# Pr_actica_1.net
KiCad netlist of a schematic drawn in EAGLE
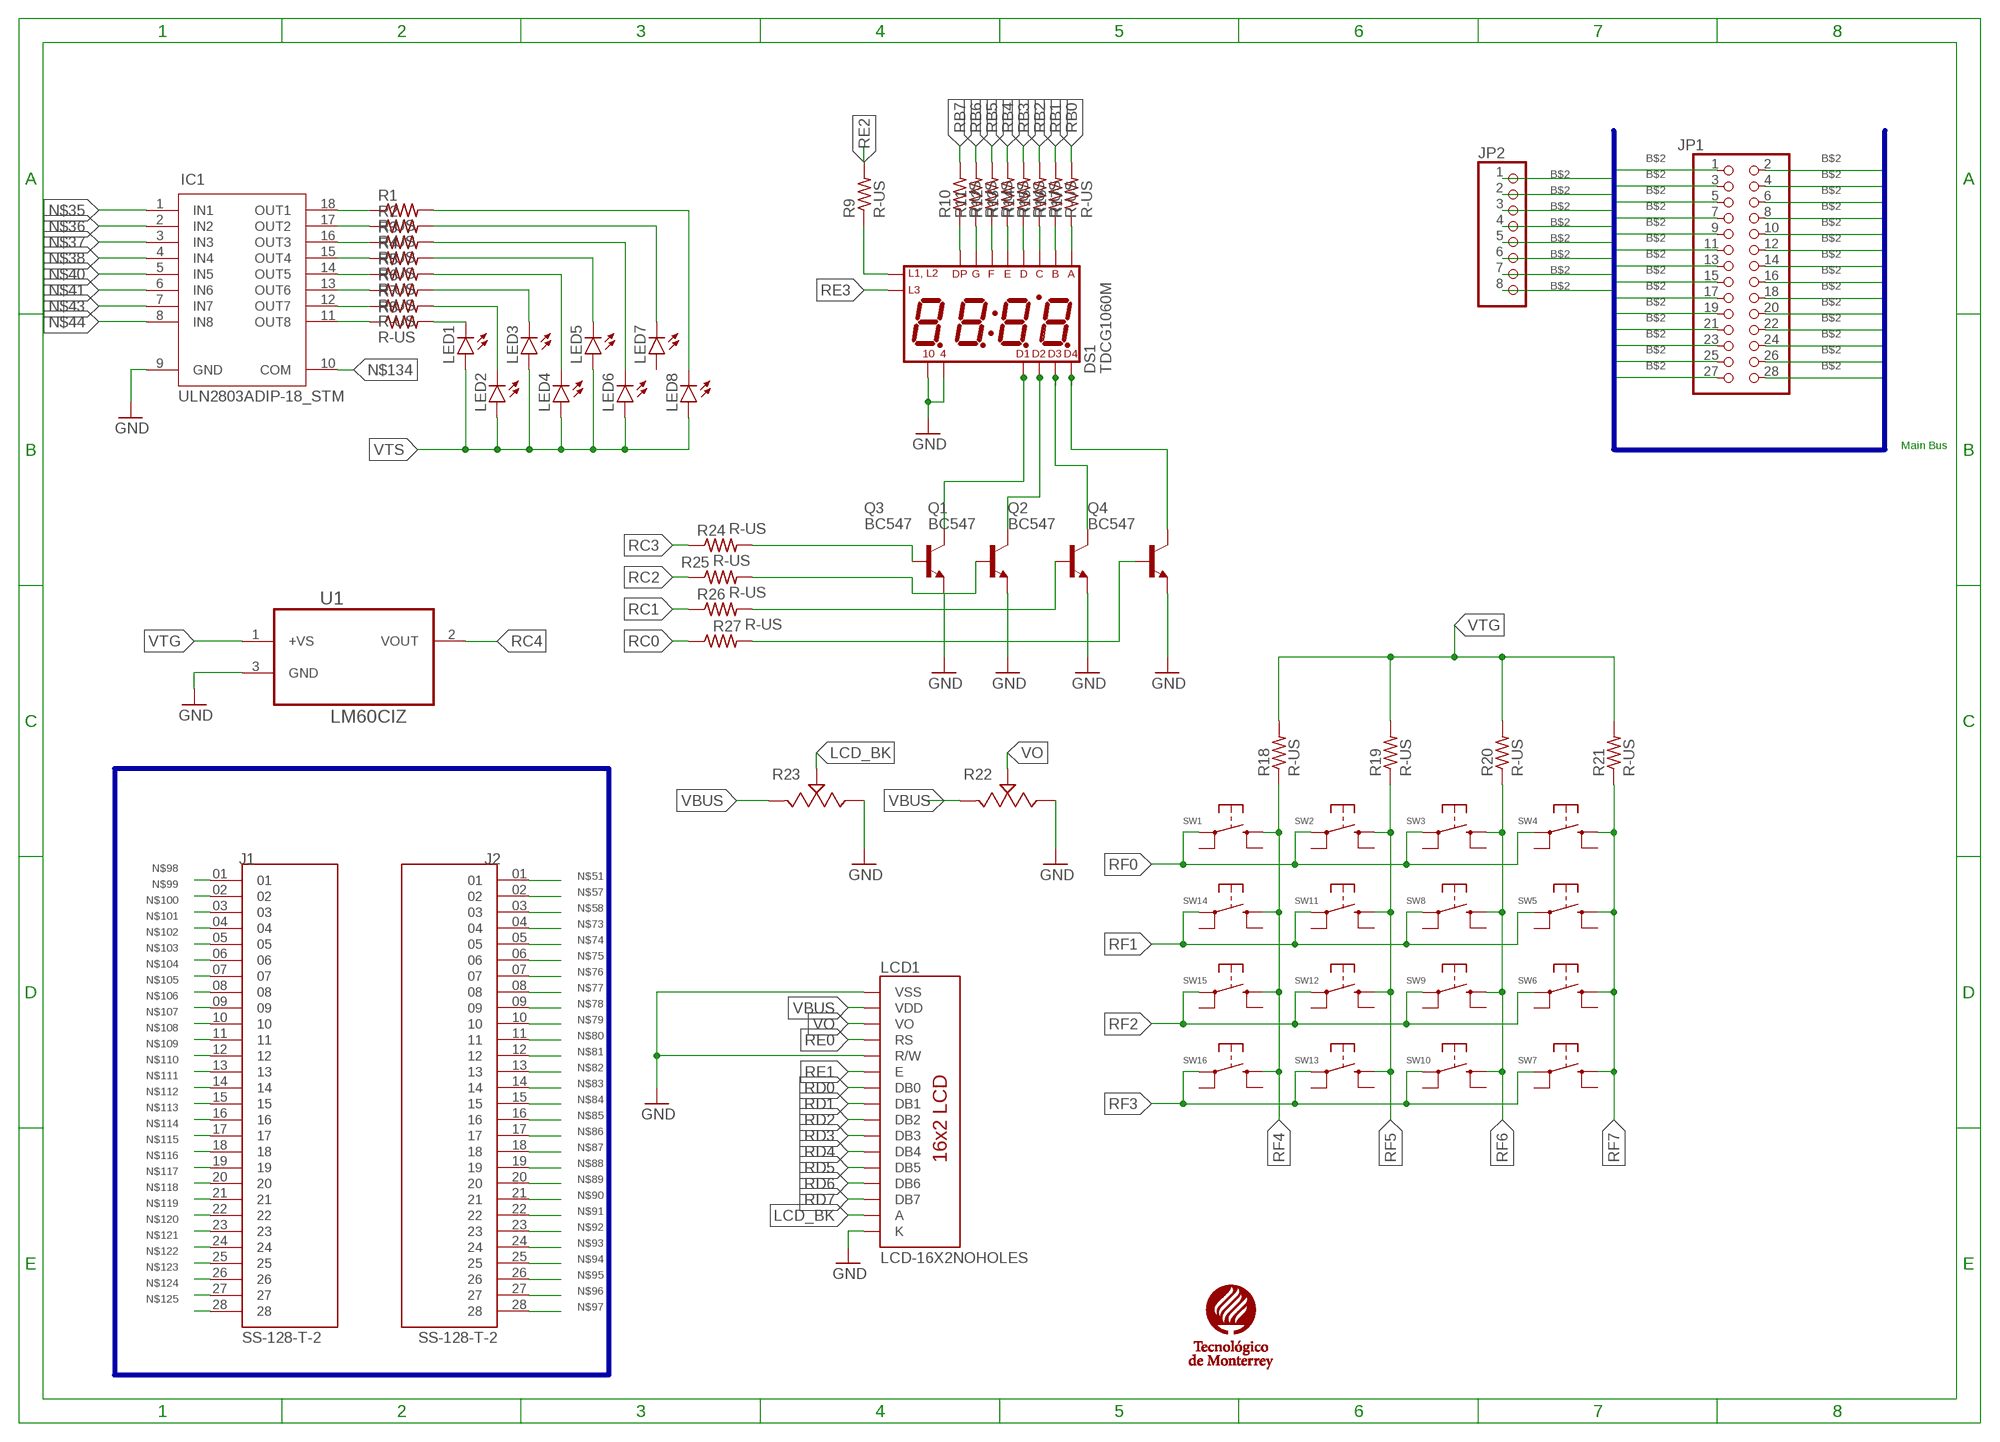
[diagram p0: schematic, sheet 1]

(export (version "E")
  (design (tool "Eeschema 10.0.6"))
  (components
    (comp (ref "DS1")
      (value "TDCG1060M")
      (footprint "eagle-import:DISPLAY_TDCG1060M")
      (fields (field (name "DIGI-KEY_PART_NUMBER") "TDCG1060M-ND") (field (name "MF") "Vishay"))
      (libsource (lib "eagle-import") (part "TDCG1060M"))
    )
    (comp (ref "IC1")
      (value "ULN2803ADIP-18_STM")
      (footprint "eagle-import:DIP-18_STM")
      (fields
        (field (name "MANUFACTURER_PART_NUMBER") "ULN2803A")
        (field (name "COPYRIGHT") "Copyright (C) 2022 Ultra Librarian. All rights reserved.")
      )
      (libsource (lib "eagle-import") (part "ULN2803ADIP-18_STM"))
    )
    (comp (ref "J1")
      (value "SS-128-T-2")
      (footprint "eagle-import:SAMTEC_SS-128-T-2")
      (fields (field (name "DIGI-KEY_PART_NUMBER") "SAM1117-28-ND") (field (name "MF") "Samtec"))
      (libsource (lib "eagle-import") (part "SS-128-T-2"))
    )
    (comp (ref "J2")
      (value "SS-128-T-2")
      (footprint "eagle-import:SAMTEC_SS-128-T-2")
      (fields (field (name "DIGI-KEY_PART_NUMBER") "SAM1117-28-ND") (field (name "MF") "Samtec"))
      (libsource (lib "eagle-import") (part "SS-128-T-2"))
    )
    (comp (ref "JP1")
      (value "PINHD-2X14-CB")
      (footprint "eagle-import:2X14-BIG")
      (libsource (lib "eagle-import") (part "PINHD-2X14-CB"))
    )
    (comp (ref "JP2")
      (value "PINHD-1X8BIG")
      (footprint "eagle-import:1X08-BIG")
      (libsource (lib "eagle-import") (part "PINHD-1X8BIG"))
    )
    (comp (ref "LCD1")
      (value "LCD-16X2NOHOLES")
      (footprint "eagle-import:LCD-16X2_NOHOLESNOSILK")
      (libsource (lib "eagle-import") (part "LCD-16X2NOHOLES"))
    )
    (comp (ref "LED1")
      (value "LED3MM")
      (footprint "eagle-import:LED3MM")
      (libsource (lib "eagle-import") (part "LED3MM"))
    )
    (comp (ref "LED2")
      (value "LED3MM")
      (footprint "eagle-import:LED3MM")
      (libsource (lib "eagle-import") (part "LED3MM"))
    )
    (comp (ref "LED3")
      (value "LED3MM")
      (footprint "eagle-import:LED3MM")
      (libsource (lib "eagle-import") (part "LED3MM"))
    )
    (comp (ref "LED4")
      (value "LED3MM")
      (footprint "eagle-import:LED3MM")
      (libsource (lib "eagle-import") (part "LED3MM"))
    )
    (comp (ref "LED5")
      (value "LED3MM")
      (footprint "eagle-import:LED3MM")
      (libsource (lib "eagle-import") (part "LED3MM"))
    )
    (comp (ref "LED6")
      (value "LED3MM")
      (footprint "eagle-import:LED3MM")
      (libsource (lib "eagle-import") (part "LED3MM"))
    )
    (comp (ref "LED7")
      (value "LED3MM")
      (footprint "eagle-import:LED3MM")
      (libsource (lib "eagle-import") (part "LED3MM"))
    )
    (comp (ref "LED8")
      (value "LED3MM")
      (footprint "eagle-import:LED3MM")
      (libsource (lib "eagle-import") (part "LED3MM"))
    )
    (comp (ref "Q1")
      (value "BC547")
      (footprint "eagle-import:TO92")
      (libsource (lib "eagle-import") (part "BC547"))
    )
    (comp (ref "Q2")
      (value "BC547")
      (footprint "eagle-import:TO92")
      (libsource (lib "eagle-import") (part "BC547"))
    )
    (comp (ref "Q3")
      (value "BC547")
      (footprint "eagle-import:TO92")
      (libsource (lib "eagle-import") (part "BC547"))
    )
    (comp (ref "Q4")
      (value "BC547")
      (footprint "eagle-import:TO92")
      (libsource (lib "eagle-import") (part "BC547"))
    )
    (comp (ref "R1")
      (value "R-US")
      (footprint "eagle-import:0207_10")
      (libsource (lib "eagle-import") (part "R-US"))
    )
    (comp (ref "R2")
      (value "R-US")
      (footprint "eagle-import:0207_10")
      (libsource (lib "eagle-import") (part "R-US"))
    )
    (comp (ref "R3")
      (value "R-US")
      (footprint "eagle-import:0207_10")
      (libsource (lib "eagle-import") (part "R-US"))
    )
    (comp (ref "R4")
      (value "R-US")
      (footprint "eagle-import:0207_10")
      (libsource (lib "eagle-import") (part "R-US"))
    )
    (comp (ref "R5")
      (value "R-US")
      (footprint "eagle-import:0207_10")
      (libsource (lib "eagle-import") (part "R-US"))
    )
    (comp (ref "R6")
      (value "R-US")
      (footprint "eagle-import:0207_10")
      (libsource (lib "eagle-import") (part "R-US"))
    )
    (comp (ref "R7")
      (value "R-US")
      (footprint "eagle-import:0207_10")
      (libsource (lib "eagle-import") (part "R-US"))
    )
    (comp (ref "R8")
      (value "R-US")
      (footprint "eagle-import:0207_10")
      (libsource (lib "eagle-import") (part "R-US"))
    )
    (comp (ref "R9")
      (value "R-US")
      (footprint "eagle-import:0207_10")
      (libsource (lib "eagle-import") (part "R-US"))
    )
    (comp (ref "R10")
      (value "R-US")
      (footprint "eagle-import:0207_10")
      (libsource (lib "eagle-import") (part "R-US"))
    )
    (comp (ref "R11")
      (value "R-US")
      (footprint "eagle-import:0207_10")
      (libsource (lib "eagle-import") (part "R-US"))
    )
    (comp (ref "R12")
      (value "R-US")
      (footprint "eagle-import:0207_10")
      (libsource (lib "eagle-import") (part "R-US"))
    )
    (comp (ref "R13")
      (value "R-US")
      (footprint "eagle-import:0207_10")
      (libsource (lib "eagle-import") (part "R-US"))
    )
    (comp (ref "R14")
      (value "R-US")
      (footprint "eagle-import:0207_10")
      (libsource (lib "eagle-import") (part "R-US"))
    )
    (comp (ref "R15")
      (value "R-US")
      (footprint "eagle-import:0207_10")
      (libsource (lib "eagle-import") (part "R-US"))
    )
    (comp (ref "R16")
      (value "R-US")
      (footprint "eagle-import:0207_10")
      (libsource (lib "eagle-import") (part "R-US"))
    )
    (comp (ref "R17")
      (value "R-US")
      (footprint "eagle-import:0207_10")
      (libsource (lib "eagle-import") (part "R-US"))
    )
    (comp (ref "R18")
      (value "R-US")
      (footprint "eagle-import:0207_10")
      (libsource (lib "eagle-import") (part "R-US"))
    )
    (comp (ref "R19")
      (value "R-US")
      (footprint "eagle-import:0207_10")
      (libsource (lib "eagle-import") (part "R-US"))
    )
    (comp (ref "R20")
      (value "R-US")
      (footprint "eagle-import:0207_10")
      (libsource (lib "eagle-import") (part "R-US"))
    )
    (comp (ref "R21")
      (value "R-US")
      (footprint "eagle-import:0207_10")
      (libsource (lib "eagle-import") (part "R-US"))
    )
    (comp (ref "R22")
      (value "3362P-1-103LF")
      (footprint "eagle-import:3362P-1-103LF")
      (fields (field (name "MANUFACTURER") "Bourns Inc.") (field (name "CREATED_PN") "PCBLayout.com"))
      (libsource (lib "eagle-import") (part "3362P-1-103LF"))
    )
    (comp (ref "R23")
      (value "3362P-1-103LF")
      (footprint "eagle-import:3362P-1-103LF")
      (fields (field (name "MANUFACTURER") "Bourns Inc.") (field (name "CREATED_PN") "PCBLayout.com"))
      (libsource (lib "eagle-import") (part "3362P-1-103LF"))
    )
    (comp (ref "R24")
      (value "R-US")
      (footprint "eagle-import:0207_10")
      (libsource (lib "eagle-import") (part "R-US"))
    )
    (comp (ref "R25")
      (value "R-US")
      (footprint "eagle-import:0207_10")
      (libsource (lib "eagle-import") (part "R-US"))
    )
    (comp (ref "R26")
      (value "R-US")
      (footprint "eagle-import:0207_10")
      (libsource (lib "eagle-import") (part "R-US"))
    )
    (comp (ref "R27")
      (value "R-US")
      (footprint "eagle-import:0207_10")
      (libsource (lib "eagle-import") (part "R-US"))
    )
    (comp (ref "SW1")
      (value "1825910-2")
      (footprint "eagle-import:TE_1825910-2")
      (fields (field (name "MF") "TE Connectivity"))
      (libsource (lib "eagle-import") (part "1825910-2"))
    )
    (comp (ref "SW2")
      (value "1825910-2")
      (footprint "eagle-import:TE_1825910-2")
      (fields (field (name "MF") "TE Connectivity"))
      (libsource (lib "eagle-import") (part "1825910-2"))
    )
    (comp (ref "SW3")
      (value "1825910-2")
      (footprint "eagle-import:TE_1825910-2")
      (fields (field (name "MF") "TE Connectivity"))
      (libsource (lib "eagle-import") (part "1825910-2"))
    )
    (comp (ref "SW4")
      (value "1825910-2")
      (footprint "eagle-import:TE_1825910-2")
      (fields (field (name "MF") "TE Connectivity"))
      (libsource (lib "eagle-import") (part "1825910-2"))
    )
    (comp (ref "SW5")
      (value "1825910-2")
      (footprint "eagle-import:TE_1825910-2")
      (fields (field (name "MF") "TE Connectivity"))
      (libsource (lib "eagle-import") (part "1825910-2"))
    )
    (comp (ref "SW6")
      (value "1825910-2")
      (footprint "eagle-import:TE_1825910-2")
      (fields (field (name "MF") "TE Connectivity"))
      (libsource (lib "eagle-import") (part "1825910-2"))
    )
    (comp (ref "SW7")
      (value "1825910-2")
      (footprint "eagle-import:TE_1825910-2")
      (fields (field (name "MF") "TE Connectivity"))
      (libsource (lib "eagle-import") (part "1825910-2"))
    )
    (comp (ref "SW8")
      (value "1825910-2")
      (footprint "eagle-import:TE_1825910-2")
      (fields (field (name "MF") "TE Connectivity"))
      (libsource (lib "eagle-import") (part "1825910-2"))
    )
    (comp (ref "SW9")
      (value "1825910-2")
      (footprint "eagle-import:TE_1825910-2")
      (fields (field (name "MF") "TE Connectivity"))
      (libsource (lib "eagle-import") (part "1825910-2"))
    )
    (comp (ref "SW10")
      (value "1825910-2")
      (footprint "eagle-import:TE_1825910-2")
      (fields (field (name "MF") "TE Connectivity"))
      (libsource (lib "eagle-import") (part "1825910-2"))
    )
    (comp (ref "SW11")
      (value "1825910-2")
      (footprint "eagle-import:TE_1825910-2")
      (fields (field (name "MF") "TE Connectivity"))
      (libsource (lib "eagle-import") (part "1825910-2"))
    )
    (comp (ref "SW12")
      (value "1825910-2")
      (footprint "eagle-import:TE_1825910-2")
      (fields (field (name "MF") "TE Connectivity"))
      (libsource (lib "eagle-import") (part "1825910-2"))
    )
    (comp (ref "SW13")
      (value "1825910-2")
      (footprint "eagle-import:TE_1825910-2")
      (fields (field (name "MF") "TE Connectivity"))
      (libsource (lib "eagle-import") (part "1825910-2"))
    )
    (comp (ref "SW14")
      (value "1825910-2")
      (footprint "eagle-import:TE_1825910-2")
      (fields (field (name "MF") "TE Connectivity"))
      (libsource (lib "eagle-import") (part "1825910-2"))
    )
    (comp (ref "SW15")
      (value "1825910-2")
      (footprint "eagle-import:TE_1825910-2")
      (fields (field (name "MF") "TE Connectivity"))
      (libsource (lib "eagle-import") (part "1825910-2"))
    )
    (comp (ref "SW16")
      (value "1825910-2")
      (footprint "eagle-import:TE_1825910-2")
      (fields (field (name "MF") "TE Connectivity"))
      (libsource (lib "eagle-import") (part "1825910-2"))
    )
    (comp (ref "TEC1")
      (value "TEC_LOGO")
      (footprint "eagle-import:TEC_LOGO")
      (libsource (lib "eagle-import") (part "TEC_LOGO"))
    )
    (comp (ref "U1")
      (value "LM60CIZ")
      (footprint "eagle-import:TO92_")
      (libsource (lib "eagle-import") (part "LM60CIZ"))
    )
  )
  (nets
    (net (code "1") (name "/B$2") (class "Default")
      (node (ref "JP1") (pin "1") (pinfunction "1_1") (pintype "passive"))
      (node (ref "JP1") (pin "10") (pinfunction "10_10") (pintype "passive"))
      (node (ref "JP1") (pin "11") (pinfunction "11_11") (pintype "passive"))
      (node (ref "JP1") (pin "12") (pinfunction "12_12") (pintype "passive"))
      (node (ref "JP1") (pin "13") (pinfunction "13_13") (pintype "passive"))
      (node (ref "JP1") (pin "14") (pinfunction "14_14") (pintype "passive"))
      (node (ref "JP1") (pin "15") (pinfunction "15_15") (pintype "passive"))
      (node (ref "JP1") (pin "16") (pinfunction "16_16") (pintype "passive"))
      (node (ref "JP1") (pin "17") (pinfunction "17_17") (pintype "passive"))
      (node (ref "JP1") (pin "18") (pinfunction "18_18") (pintype "passive"))
      (node (ref "JP1") (pin "19") (pinfunction "19_19") (pintype "passive"))
      (node (ref "JP1") (pin "2") (pinfunction "2_2") (pintype "passive"))
      (node (ref "JP1") (pin "20") (pinfunction "20_20") (pintype "passive"))
      (node (ref "JP1") (pin "21") (pinfunction "21_21") (pintype "passive"))
      (node (ref "JP1") (pin "22") (pinfunction "22_22") (pintype "passive"))
      (node (ref "JP1") (pin "23") (pinfunction "23_23") (pintype "passive"))
      (node (ref "JP1") (pin "24") (pinfunction "24_24") (pintype "passive"))
      (node (ref "JP1") (pin "25") (pinfunction "25_25") (pintype "passive"))
      (node (ref "JP1") (pin "26") (pinfunction "26_26") (pintype "passive"))
      (node (ref "JP1") (pin "27") (pinfunction "27_27") (pintype "passive"))
      (node (ref "JP1") (pin "28") (pinfunction "28_28") (pintype "passive"))
      (node (ref "JP1") (pin "3") (pinfunction "3_3") (pintype "passive"))
      (node (ref "JP1") (pin "4") (pinfunction "4_4") (pintype "passive"))
      (node (ref "JP1") (pin "5") (pinfunction "5_5") (pintype "passive"))
      (node (ref "JP1") (pin "6") (pinfunction "6_6") (pintype "passive"))
      (node (ref "JP1") (pin "7") (pinfunction "7_7") (pintype "passive"))
      (node (ref "JP1") (pin "8") (pinfunction "8_8") (pintype "passive"))
      (node (ref "JP1") (pin "9") (pinfunction "9_9") (pintype "passive"))
      (node (ref "JP2") (pin "1") (pinfunction "1_1") (pintype "passive"))
      (node (ref "JP2") (pin "2") (pinfunction "2_2") (pintype "passive"))
      (node (ref "JP2") (pin "3") (pinfunction "3_3") (pintype "passive"))
      (node (ref "JP2") (pin "4") (pinfunction "4_4") (pintype "passive"))
      (node (ref "JP2") (pin "5") (pinfunction "5_5") (pintype "passive"))
      (node (ref "JP2") (pin "6") (pinfunction "6_6") (pintype "passive"))
      (node (ref "JP2") (pin "7") (pinfunction "7_7") (pintype "passive"))
      (node (ref "JP2") (pin "8") (pinfunction "8_8") (pintype "passive"))
    )
    (net (code "2") (name "/N$51") (class "Default")
      (node (ref "J2") (pin "01") (pinfunction "01_01") (pintype "passive"))
    )
    (net (code "3") (name "/N$57") (class "Default")
      (node (ref "J2") (pin "02") (pinfunction "02_02") (pintype "passive"))
    )
    (net (code "4") (name "/N$58") (class "Default")
      (node (ref "J2") (pin "03") (pinfunction "03_03") (pintype "passive"))
    )
    (net (code "5") (name "/N$73") (class "Default")
      (node (ref "J2") (pin "04") (pinfunction "04_04") (pintype "passive"))
    )
    (net (code "6") (name "/N$74") (class "Default")
      (node (ref "J2") (pin "05") (pinfunction "05_05") (pintype "passive"))
    )
    (net (code "7") (name "/N$75") (class "Default")
      (node (ref "J2") (pin "06") (pinfunction "06_06") (pintype "passive"))
    )
    (net (code "8") (name "/N$76") (class "Default")
      (node (ref "J2") (pin "07") (pinfunction "07_07") (pintype "passive"))
    )
    (net (code "9") (name "/N$77") (class "Default")
      (node (ref "J2") (pin "08") (pinfunction "08_08") (pintype "passive"))
    )
    (net (code "10") (name "/N$78") (class "Default")
      (node (ref "J2") (pin "09") (pinfunction "09_09") (pintype "passive"))
    )
    (net (code "11") (name "/N$79") (class "Default")
      (node (ref "J2") (pin "10") (pinfunction "10_10") (pintype "passive"))
    )
    (net (code "12") (name "/N$80") (class "Default")
      (node (ref "J2") (pin "11") (pinfunction "11_11") (pintype "passive"))
    )
    (net (code "13") (name "/N$81") (class "Default")
      (node (ref "J2") (pin "12") (pinfunction "12_12") (pintype "passive"))
    )
    (net (code "14") (name "/N$82") (class "Default")
      (node (ref "J2") (pin "13") (pinfunction "13_13") (pintype "passive"))
    )
    (net (code "15") (name "/N$83") (class "Default")
      (node (ref "J2") (pin "14") (pinfunction "14_14") (pintype "passive"))
    )
    (net (code "16") (name "/N$84") (class "Default")
      (node (ref "J2") (pin "15") (pinfunction "15_15") (pintype "passive"))
    )
    (net (code "17") (name "/N$85") (class "Default")
      (node (ref "J2") (pin "16") (pinfunction "16_16") (pintype "passive"))
    )
    (net (code "18") (name "/N$86") (class "Default")
      (node (ref "J2") (pin "17") (pinfunction "17_17") (pintype "passive"))
    )
    (net (code "19") (name "/N$87") (class "Default")
      (node (ref "J2") (pin "18") (pinfunction "18_18") (pintype "passive"))
    )
    (net (code "20") (name "/N$88") (class "Default")
      (node (ref "J2") (pin "19") (pinfunction "19_19") (pintype "passive"))
    )
    (net (code "21") (name "/N$89") (class "Default")
      (node (ref "J2") (pin "20") (pinfunction "20_20") (pintype "passive"))
    )
    (net (code "22") (name "/N$90") (class "Default")
      (node (ref "J2") (pin "21") (pinfunction "21_21") (pintype "passive"))
    )
    (net (code "23") (name "/N$91") (class "Default")
      (node (ref "J2") (pin "22") (pinfunction "22_22") (pintype "passive"))
    )
    (net (code "24") (name "/N$92") (class "Default")
      (node (ref "J2") (pin "23") (pinfunction "23_23") (pintype "passive"))
    )
    (net (code "25") (name "/N$93") (class "Default")
      (node (ref "J2") (pin "24") (pinfunction "24_24") (pintype "passive"))
    )
    (net (code "26") (name "/N$94") (class "Default")
      (node (ref "J2") (pin "25") (pinfunction "25_25") (pintype "passive"))
    )
    (net (code "27") (name "/N$95") (class "Default")
      (node (ref "J2") (pin "26") (pinfunction "26_26") (pintype "passive"))
    )
    (net (code "28") (name "/N$96") (class "Default")
      (node (ref "J2") (pin "27") (pinfunction "27_27") (pintype "passive"))
    )
    (net (code "29") (name "/N$97") (class "Default")
      (node (ref "J2") (pin "28") (pinfunction "28_28") (pintype "passive"))
    )
    (net (code "30") (name "/N$98") (class "Default")
      (node (ref "J1") (pin "01") (pinfunction "01_01") (pintype "passive"))
    )
    (net (code "31") (name "/N$99") (class "Default")
      (node (ref "J1") (pin "02") (pinfunction "02_02") (pintype "passive"))
    )
    (net (code "32") (name "/N$100") (class "Default")
      (node (ref "J1") (pin "03") (pinfunction "03_03") (pintype "passive"))
    )
    (net (code "33") (name "/N$101") (class "Default")
      (node (ref "J1") (pin "04") (pinfunction "04_04") (pintype "passive"))
    )
    (net (code "34") (name "/N$102") (class "Default")
      (node (ref "J1") (pin "05") (pinfunction "05_05") (pintype "passive"))
    )
    (net (code "35") (name "/N$103") (class "Default")
      (node (ref "J1") (pin "06") (pinfunction "06_06") (pintype "passive"))
    )
    (net (code "36") (name "/N$104") (class "Default")
      (node (ref "J1") (pin "07") (pinfunction "07_07") (pintype "passive"))
    )
    (net (code "37") (name "/N$105") (class "Default")
      (node (ref "J1") (pin "08") (pinfunction "08_08") (pintype "passive"))
    )
    (net (code "38") (name "/N$106") (class "Default")
      (node (ref "J1") (pin "09") (pinfunction "09_09") (pintype "passive"))
    )
    (net (code "39") (name "/N$107") (class "Default")
      (node (ref "J1") (pin "10") (pinfunction "10_10") (pintype "passive"))
    )
    (net (code "40") (name "/N$108") (class "Default")
      (node (ref "J1") (pin "11") (pinfunction "11_11") (pintype "passive"))
    )
    (net (code "41") (name "/N$109") (class "Default")
      (node (ref "J1") (pin "12") (pinfunction "12_12") (pintype "passive"))
    )
    (net (code "42") (name "/N$110") (class "Default")
      (node (ref "J1") (pin "13") (pinfunction "13_13") (pintype "passive"))
    )
    (net (code "43") (name "/N$111") (class "Default")
      (node (ref "J1") (pin "14") (pinfunction "14_14") (pintype "passive"))
    )
    (net (code "44") (name "/N$112") (class "Default")
      (node (ref "J1") (pin "15") (pinfunction "15_15") (pintype "passive"))
    )
    (net (code "45") (name "/N$113") (class "Default")
      (node (ref "J1") (pin "16") (pinfunction "16_16") (pintype "passive"))
    )
    (net (code "46") (name "/N$114") (class "Default")
      (node (ref "J1") (pin "17") (pinfunction "17_17") (pintype "passive"))
    )
    (net (code "47") (name "/N$115") (class "Default")
      (node (ref "J1") (pin "18") (pinfunction "18_18") (pintype "passive"))
    )
    (net (code "48") (name "/N$116") (class "Default")
      (node (ref "J1") (pin "19") (pinfunction "19_19") (pintype "passive"))
    )
    (net (code "49") (name "/N$117") (class "Default")
      (node (ref "J1") (pin "20") (pinfunction "20_20") (pintype "passive"))
    )
    (net (code "50") (name "/N$118") (class "Default")
      (node (ref "J1") (pin "21") (pinfunction "21_21") (pintype "passive"))
    )
    (net (code "51") (name "/N$119") (class "Default")
      (node (ref "J1") (pin "22") (pinfunction "22_22") (pintype "passive"))
    )
    (net (code "52") (name "/N$120") (class "Default")
      (node (ref "J1") (pin "23") (pinfunction "23_23") (pintype "passive"))
    )
    (net (code "53") (name "/N$121") (class "Default")
      (node (ref "J1") (pin "24") (pinfunction "24_24") (pintype "passive"))
    )
    (net (code "54") (name "/N$122") (class "Default")
      (node (ref "J1") (pin "25") (pinfunction "25_25") (pintype "passive"))
    )
    (net (code "55") (name "/N$123") (class "Default")
      (node (ref "J1") (pin "26") (pinfunction "26_26") (pintype "passive"))
    )
    (net (code "56") (name "/N$124") (class "Default")
      (node (ref "J1") (pin "27") (pinfunction "27_27") (pintype "passive"))
    )
    (net (code "57") (name "/N$125") (class "Default")
      (node (ref "J1") (pin "28") (pinfunction "28_28") (pintype "passive"))
    )
    (net (code "58") (name "GND") (class "Default")
      (node (ref "DS1") (pin "10") (pinfunction "10_10") (pintype "passive"))
      (node (ref "DS1") (pin "4") (pinfunction "4_4") (pintype "passive"))
      (node (ref "IC1") (pin "9") (pinfunction "GND_9") (pintype "power_in"))
      (node (ref "LCD1") (pin "1") (pinfunction "VSS_1") (pintype "power_in"))
      (node (ref "LCD1") (pin "16") (pinfunction "K_16") (pintype "power_in"))
      (node (ref "LCD1") (pin "5") (pinfunction "R/W_5") (pintype "input"))
      (node (ref "Q1") (pin "1") (pinfunction "E_1") (pintype "passive"))
      (node (ref "Q2") (pin "1") (pinfunction "E_1") (pintype "passive"))
      (node (ref "Q3") (pin "1") (pinfunction "E_1") (pintype "passive"))
      (node (ref "Q4") (pin "1") (pinfunction "E_1") (pintype "passive"))
      (node (ref "R22") (pin "3") (pinfunction "3_3") (pintype "passive"))
      (node (ref "R23") (pin "3") (pinfunction "3_3") (pintype "passive"))
      (node (ref "U1") (pin "3") (pinfunction "GND_3") (pintype "passive"))
    )
    (net (code "59") (name "LCD_BK") (class "Default")
      (node (ref "LCD1") (pin "15") (pinfunction "A_15") (pintype "power_in"))
      (node (ref "R23") (pin "2") (pinfunction "2_2") (pintype "passive"))
    )
    (net (code "60") (name "N$35") (class "Default")
      (node (ref "IC1") (pin "1") (pinfunction "IN1_1") (pintype "input"))
    )
    (net (code "61") (name "N$36") (class "Default")
      (node (ref "IC1") (pin "2") (pinfunction "IN2_2") (pintype "input"))
    )
    (net (code "62") (name "N$37") (class "Default")
      (node (ref "IC1") (pin "3") (pinfunction "IN3_3") (pintype "input"))
    )
    (net (code "63") (name "N$38") (class "Default")
      (node (ref "IC1") (pin "4") (pinfunction "IN4_4") (pintype "input"))
    )
    (net (code "64") (name "N$40") (class "Default")
      (node (ref "IC1") (pin "5") (pinfunction "IN5_5") (pintype "input"))
    )
    (net (code "65") (name "N$41") (class "Default")
      (node (ref "IC1") (pin "6") (pinfunction "IN6_6") (pintype "input"))
    )
    (net (code "66") (name "N$43") (class "Default")
      (node (ref "IC1") (pin "7") (pinfunction "IN7_7") (pintype "input"))
    )
    (net (code "67") (name "N$44") (class "Default")
      (node (ref "IC1") (pin "8") (pinfunction "IN8_8") (pintype "input"))
    )
    (net (code "68") (name "N$134") (class "Default")
      (node (ref "IC1") (pin "10") (pinfunction "COM_10") (pintype "passive"))
    )
    (net (code "69") (name "Net-(DS1-A)") (class "Default")
      (node (ref "DS1") (pin "14") (pinfunction "A_14") (pintype "passive"))
      (node (ref "R17") (pin "1") (pinfunction "1_1") (pintype "passive"))
    )
    (net (code "70") (name "Net-(DS1-B)") (class "Default")
      (node (ref "DS1") (pin "16") (pinfunction "B_16") (pintype "passive"))
      (node (ref "R16") (pin "1") (pinfunction "1_1") (pintype "passive"))
    )
    (net (code "71") (name "Net-(DS1-C)") (class "Default")
      (node (ref "DS1") (pin "13") (pinfunction "C_13") (pintype "passive"))
      (node (ref "R15") (pin "1") (pinfunction "1_1") (pintype "passive"))
    )
    (net (code "72") (name "Net-(DS1-D)") (class "Default")
      (node (ref "DS1") (pin "3") (pinfunction "D_3") (pintype "passive"))
      (node (ref "R14") (pin "1") (pinfunction "1_1") (pintype "passive"))
    )
    (net (code "73") (name "Net-(DS1-DIG1)") (class "Default")
      (node (ref "DS1") (pin "1") (pinfunction "DIG1_1") (pintype "passive"))
      (node (ref "Q3") (pin "3") (pinfunction "C_3") (pintype "passive"))
    )
    (net (code "74") (name "Net-(DS1-DIG2)") (class "Default")
      (node (ref "DS1") (pin "2") (pinfunction "DIG2_2") (pintype "passive"))
      (node (ref "Q1") (pin "3") (pinfunction "C_3") (pintype "passive"))
    )
    (net (code "75") (name "Net-(DS1-DIG3)") (class "Default")
      (node (ref "DS1") (pin "6") (pinfunction "DIG3_6") (pintype "passive"))
      (node (ref "Q2") (pin "3") (pinfunction "C_3") (pintype "passive"))
    )
    (net (code "76") (name "Net-(DS1-DIG4)") (class "Default")
      (node (ref "DS1") (pin "8") (pinfunction "DIG4_8") (pintype "passive"))
      (node (ref "Q4") (pin "3") (pinfunction "C_3") (pintype "passive"))
    )
    (net (code "77") (name "Net-(DS1-DP)") (class "Default")
      (node (ref "DS1") (pin "7") (pinfunction "DP_7") (pintype "passive"))
      (node (ref "R10") (pin "1") (pinfunction "1_1") (pintype "passive"))
    )
    (net (code "78") (name "Net-(DS1-E)") (class "Default")
      (node (ref "DS1") (pin "5") (pinfunction "E_5") (pintype "passive"))
      (node (ref "R13") (pin "1") (pinfunction "1_1") (pintype "passive"))
    )
    (net (code "79") (name "Net-(DS1-F)") (class "Default")
      (node (ref "DS1") (pin "11") (pinfunction "F_11") (pintype "passive"))
      (node (ref "R12") (pin "1") (pinfunction "1_1") (pintype "passive"))
    )
    (net (code "80") (name "Net-(DS1-G)") (class "Default")
      (node (ref "DS1") (pin "15") (pinfunction "G_15") (pintype "passive"))
      (node (ref "R11") (pin "1") (pinfunction "1_1") (pintype "passive"))
    )
    (net (code "81") (name "Net-(DS1-L1_L2)") (class "Default")
      (node (ref "DS1") (pin "12") (pinfunction "L1_L2_12") (pintype "passive"))
      (node (ref "R9") (pin "1") (pinfunction "1_1") (pintype "passive"))
    )
    (net (code "82") (name "Net-(IC1-OUT1)") (class "Default")
      (node (ref "IC1") (pin "18") (pinfunction "OUT1_18") (pintype "passive"))
      (node (ref "R1") (pin "1") (pinfunction "1_1") (pintype "passive"))
    )
    (net (code "83") (name "Net-(IC1-OUT2)") (class "Default")
      (node (ref "IC1") (pin "17") (pinfunction "OUT2_17") (pintype "passive"))
      (node (ref "R2") (pin "1") (pinfunction "1_1") (pintype "passive"))
    )
    (net (code "84") (name "Net-(IC1-OUT3)") (class "Default")
      (node (ref "IC1") (pin "16") (pinfunction "OUT3_16") (pintype "passive"))
      (node (ref "R3") (pin "1") (pinfunction "1_1") (pintype "passive"))
    )
    (net (code "85") (name "Net-(IC1-OUT4)") (class "Default")
      (node (ref "IC1") (pin "15") (pinfunction "OUT4_15") (pintype "passive"))
      (node (ref "R4") (pin "1") (pinfunction "1_1") (pintype "passive"))
    )
    (net (code "86") (name "Net-(IC1-OUT5)") (class "Default")
      (node (ref "IC1") (pin "14") (pinfunction "OUT5_14") (pintype "passive"))
      (node (ref "R5") (pin "1") (pinfunction "1_1") (pintype "passive"))
    )
    (net (code "87") (name "Net-(IC1-OUT6)") (class "Default")
      (node (ref "IC1") (pin "13") (pinfunction "OUT6_13") (pintype "passive"))
      (node (ref "R6") (pin "1") (pinfunction "1_1") (pintype "passive"))
    )
    (net (code "88") (name "Net-(IC1-OUT7)") (class "Default")
      (node (ref "IC1") (pin "12") (pinfunction "OUT7_12") (pintype "passive"))
      (node (ref "R7") (pin "1") (pinfunction "1_1") (pintype "passive"))
    )
    (net (code "89") (name "Net-(IC1-OUT8)") (class "Default")
      (node (ref "IC1") (pin "11") (pinfunction "OUT8_11") (pintype "passive"))
      (node (ref "R8") (pin "1") (pinfunction "1_1") (pintype "passive"))
    )
    (net (code "90") (name "Net-(LED1-C)") (class "Default")
      (node (ref "LED1") (pin "K") (pinfunction "C_K") (pintype "passive"))
      (node (ref "R8") (pin "2") (pinfunction "2_2") (pintype "passive"))
    )
    (net (code "91") (name "Net-(LED2-C)") (class "Default")
      (node (ref "LED2") (pin "K") (pinfunction "C_K") (pintype "passive"))
      (node (ref "R7") (pin "2") (pinfunction "2_2") (pintype "passive"))
    )
    (net (code "92") (name "Net-(LED3-C)") (class "Default")
      (node (ref "LED3") (pin "K") (pinfunction "C_K") (pintype "passive"))
      (node (ref "R6") (pin "2") (pinfunction "2_2") (pintype "passive"))
    )
    (net (code "93") (name "Net-(LED4-C)") (class "Default")
      (node (ref "LED4") (pin "K") (pinfunction "C_K") (pintype "passive"))
      (node (ref "R5") (pin "2") (pinfunction "2_2") (pintype "passive"))
    )
    (net (code "94") (name "Net-(LED5-C)") (class "Default")
      (node (ref "LED5") (pin "K") (pinfunction "C_K") (pintype "passive"))
      (node (ref "R4") (pin "2") (pinfunction "2_2") (pintype "passive"))
    )
    (net (code "95") (name "Net-(LED6-C)") (class "Default")
      (node (ref "LED6") (pin "K") (pinfunction "C_K") (pintype "passive"))
      (node (ref "R3") (pin "2") (pinfunction "2_2") (pintype "passive"))
    )
    (net (code "96") (name "Net-(LED7-C)") (class "Default")
      (node (ref "LED7") (pin "K") (pinfunction "C_K") (pintype "passive"))
      (node (ref "R2") (pin "2") (pinfunction "2_2") (pintype "passive"))
    )
    (net (code "97") (name "Net-(LED8-C)") (class "Default")
      (node (ref "LED8") (pin "K") (pinfunction "C_K") (pintype "passive"))
      (node (ref "R1") (pin "2") (pinfunction "2_2") (pintype "passive"))
    )
    (net (code "98") (name "Net-(Q1-B)") (class "Default")
      (node (ref "Q1") (pin "2") (pinfunction "B_2") (pintype "passive"))
      (node (ref "R25") (pin "2") (pinfunction "2_2") (pintype "passive"))
    )
    (net (code "99") (name "Net-(Q2-B)") (class "Default")
      (node (ref "Q2") (pin "2") (pinfunction "B_2") (pintype "passive"))
      (node (ref "R26") (pin "2") (pinfunction "2_2") (pintype "passive"))
    )
    (net (code "100") (name "Net-(Q3-B)") (class "Default")
      (node (ref "Q3") (pin "2") (pinfunction "B_2") (pintype "passive"))
      (node (ref "R24") (pin "2") (pinfunction "2_2") (pintype "passive"))
    )
    (net (code "101") (name "Net-(Q4-B)") (class "Default")
      (node (ref "Q4") (pin "2") (pinfunction "B_2") (pintype "passive"))
      (node (ref "R27") (pin "2") (pinfunction "2_2") (pintype "passive"))
    )
    (net (code "102") (name "RB0") (class "Default")
      (node (ref "R17") (pin "2") (pinfunction "2_2") (pintype "passive"))
    )
    (net (code "103") (name "RB1") (class "Default")
      (node (ref "R16") (pin "2") (pinfunction "2_2") (pintype "passive"))
    )
    (net (code "104") (name "RB2") (class "Default")
      (node (ref "R15") (pin "2") (pinfunction "2_2") (pintype "passive"))
    )
    (net (code "105") (name "RB3") (class "Default")
      (node (ref "R14") (pin "2") (pinfunction "2_2") (pintype "passive"))
    )
    (net (code "106") (name "RB4") (class "Default")
      (node (ref "R13") (pin "2") (pinfunction "2_2") (pintype "passive"))
    )
    (net (code "107") (name "RB5") (class "Default")
      (node (ref "R12") (pin "2") (pinfunction "2_2") (pintype "passive"))
    )
    (net (code "108") (name "RB6") (class "Default")
      (node (ref "R11") (pin "2") (pinfunction "2_2") (pintype "passive"))
    )
    (net (code "109") (name "RB7") (class "Default")
      (node (ref "R10") (pin "2") (pinfunction "2_2") (pintype "passive"))
    )
    (net (code "110") (name "RC0") (class "Default")
      (node (ref "R27") (pin "1") (pinfunction "1_1") (pintype "passive"))
    )
    (net (code "111") (name "RC1") (class "Default")
      (node (ref "R26") (pin "1") (pinfunction "1_1") (pintype "passive"))
    )
    (net (code "112") (name "RC2") (class "Default")
      (node (ref "R25") (pin "1") (pinfunction "1_1") (pintype "passive"))
    )
    (net (code "113") (name "RC3") (class "Default")
      (node (ref "R24") (pin "1") (pinfunction "1_1") (pintype "passive"))
    )
    (net (code "114") (name "RC4") (class "Default")
      (node (ref "U1") (pin "2") (pinfunction "VOUT_2") (pintype "output"))
    )
    (net (code "115") (name "RD0") (class "Default")
      (node (ref "LCD1") (pin "7") (pinfunction "DB0_7") (pintype "bidirectional"))
    )
    (net (code "116") (name "RD1") (class "Default")
      (node (ref "LCD1") (pin "8") (pinfunction "DB1_8") (pintype "bidirectional"))
    )
    (net (code "117") (name "RD2") (class "Default")
      (node (ref "LCD1") (pin "9") (pinfunction "DB2_9") (pintype "bidirectional"))
    )
    (net (code "118") (name "RD3") (class "Default")
      (node (ref "LCD1") (pin "10") (pinfunction "DB3_10") (pintype "bidirectional"))
    )
    (net (code "119") (name "RD4") (class "Default")
      (node (ref "LCD1") (pin "11") (pinfunction "DB4_11") (pintype "bidirectional"))
    )
    (net (code "120") (name "RD5") (class "Default")
      (node (ref "LCD1") (pin "12") (pinfunction "DB5_12") (pintype "bidirectional"))
    )
    (net (code "121") (name "RD6") (class "Default")
      (node (ref "LCD1") (pin "13") (pinfunction "DB6_13") (pintype "bidirectional"))
    )
    (net (code "122") (name "RD7") (class "Default")
      (node (ref "LCD1") (pin "14") (pinfunction "DB7_14") (pintype "bidirectional"))
    )
    (net (code "123") (name "RE0") (class "Default")
      (node (ref "LCD1") (pin "4") (pinfunction "RS_4") (pintype "input"))
    )
    (net (code "124") (name "RE1") (class "Default")
      (node (ref "LCD1") (pin "6") (pinfunction "E_6") (pintype "input"))
    )
    (net (code "125") (name "RE2") (class "Default")
      (node (ref "R9") (pin "2") (pinfunction "2_2") (pintype "passive"))
    )
    (net (code "126") (name "RE3") (class "Default")
      (node (ref "DS1") (pin "9") (pinfunction "L3_9") (pintype "passive"))
    )
    (net (code "127") (name "RF0") (class "Default")
      (node (ref "SW1") (pin "1") (pinfunction "P_1") (pintype "passive"))
      (node (ref "SW2") (pin "1") (pinfunction "P_1") (pintype "passive"))
      (node (ref "SW3") (pin "1") (pinfunction "P_1") (pintype "passive"))
      (node (ref "SW4") (pin "1") (pinfunction "P_1") (pintype "passive"))
    )
    (net (code "128") (name "RF1") (class "Default")
      (node (ref "SW11") (pin "1") (pinfunction "P_1") (pintype "passive"))
      (node (ref "SW14") (pin "1") (pinfunction "P_1") (pintype "passive"))
      (node (ref "SW5") (pin "1") (pinfunction "P_1") (pintype "passive"))
      (node (ref "SW8") (pin "1") (pinfunction "P_1") (pintype "passive"))
    )
    (net (code "129") (name "RF2") (class "Default")
      (node (ref "SW12") (pin "1") (pinfunction "P_1") (pintype "passive"))
      (node (ref "SW15") (pin "1") (pinfunction "P_1") (pintype "passive"))
      (node (ref "SW6") (pin "1") (pinfunction "P_1") (pintype "passive"))
      (node (ref "SW9") (pin "1") (pinfunction "P_1") (pintype "passive"))
    )
    (net (code "130") (name "RF3") (class "Default")
      (node (ref "SW10") (pin "1") (pinfunction "P_1") (pintype "passive"))
      (node (ref "SW13") (pin "1") (pinfunction "P_1") (pintype "passive"))
      (node (ref "SW16") (pin "1") (pinfunction "P_1") (pintype "passive"))
      (node (ref "SW7") (pin "1") (pinfunction "P_1") (pintype "passive"))
    )
    (net (code "131") (name "RF4") (class "Default")
      (node (ref "R18") (pin "1") (pinfunction "1_1") (pintype "passive"))
      (node (ref "SW1") (pin "2") (pinfunction "S_2") (pintype "passive"))
      (node (ref "SW14") (pin "2") (pinfunction "S_2") (pintype "passive"))
      (node (ref "SW15") (pin "2") (pinfunction "S_2") (pintype "passive"))
      (node (ref "SW16") (pin "2") (pinfunction "S_2") (pintype "passive"))
    )
    (net (code "132") (name "RF5") (class "Default")
      (node (ref "R19") (pin "1") (pinfunction "1_1") (pintype "passive"))
      (node (ref "SW11") (pin "2") (pinfunction "S_2") (pintype "passive"))
      (node (ref "SW12") (pin "2") (pinfunction "S_2") (pintype "passive"))
      (node (ref "SW13") (pin "2") (pinfunction "S_2") (pintype "passive"))
      (node (ref "SW2") (pin "2") (pinfunction "S_2") (pintype "passive"))
    )
    (net (code "133") (name "RF6") (class "Default")
      (node (ref "R20") (pin "1") (pinfunction "1_1") (pintype "passive"))
      (node (ref "SW10") (pin "2") (pinfunction "S_2") (pintype "passive"))
      (node (ref "SW3") (pin "2") (pinfunction "S_2") (pintype "passive"))
      (node (ref "SW8") (pin "2") (pinfunction "S_2") (pintype "passive"))
      (node (ref "SW9") (pin "2") (pinfunction "S_2") (pintype "passive"))
    )
    (net (code "134") (name "RF7") (class "Default")
      (node (ref "R21") (pin "1") (pinfunction "1_1") (pintype "passive"))
      (node (ref "SW4") (pin "2") (pinfunction "S_2") (pintype "passive"))
      (node (ref "SW5") (pin "2") (pinfunction "S_2") (pintype "passive"))
      (node (ref "SW6") (pin "2") (pinfunction "S_2") (pintype "passive"))
      (node (ref "SW7") (pin "2") (pinfunction "S_2") (pintype "passive"))
    )
    (net (code "135") (name "VBUS") (class "Default")
      (node (ref "LCD1") (pin "2") (pinfunction "VDD_2") (pintype "power_in"))
      (node (ref "R22") (pin "1") (pinfunction "1_1") (pintype "passive"))
      (node (ref "R23") (pin "1") (pinfunction "1_1") (pintype "passive"))
    )
    (net (code "136") (name "VO") (class "Default")
      (node (ref "LCD1") (pin "3") (pinfunction "VO_3") (pintype "bidirectional"))
      (node (ref "R22") (pin "2") (pinfunction "2_2") (pintype "passive"))
    )
    (net (code "137") (name "VTG") (class "Default")
      (node (ref "R18") (pin "2") (pinfunction "2_2") (pintype "passive"))
      (node (ref "R19") (pin "2") (pinfunction "2_2") (pintype "passive"))
      (node (ref "R20") (pin "2") (pinfunction "2_2") (pintype "passive"))
      (node (ref "R21") (pin "2") (pinfunction "2_2") (pintype "passive"))
      (node (ref "U1") (pin "1") (pinfunction "+VS_1") (pintype "power_in"))
    )
    (net (code "138") (name "VTS") (class "Default")
      (node (ref "LED1") (pin "A") (pinfunction "A_A") (pintype "passive"))
      (node (ref "LED2") (pin "A") (pinfunction "A_A") (pintype "passive"))
      (node (ref "LED3") (pin "A") (pinfunction "A_A") (pintype "passive"))
      (node (ref "LED4") (pin "A") (pinfunction "A_A") (pintype "passive"))
      (node (ref "LED5") (pin "A") (pinfunction "A_A") (pintype "passive"))
      (node (ref "LED6") (pin "A") (pinfunction "A_A") (pintype "passive"))
      (node (ref "LED8") (pin "A") (pinfunction "A_A") (pintype "passive"))
    )
    (net (code "139") (name "unconnected-(LED7-PadA)") (class "Default")
      (node (ref "LED7") (pin "A") (pinfunction "A_A") (pintype "passive"))
    )
    (net (code "140") (name "unconnected-(SW1-P1-Pad3)") (class "Default")
      (node (ref "SW1") (pin "3") (pinfunction "P1_3") (pintype "passive"))
    )
    (net (code "141") (name "unconnected-(SW1-S1-Pad4)") (class "Default")
      (node (ref "SW1") (pin "4") (pinfunction "S1_4") (pintype "passive"))
    )
    (net (code "142") (name "unconnected-(SW2-P1-Pad3)") (class "Default")
      (node (ref "SW2") (pin "3") (pinfunction "P1_3") (pintype "passive"))
    )
    (net (code "143") (name "unconnected-(SW2-S1-Pad4)") (class "Default")
      (node (ref "SW2") (pin "4") (pinfunction "S1_4") (pintype "passive"))
    )
    (net (code "144") (name "unconnected-(SW3-P1-Pad3)") (class "Default")
      (node (ref "SW3") (pin "3") (pinfunction "P1_3") (pintype "passive"))
    )
    (net (code "145") (name "unconnected-(SW3-S1-Pad4)") (class "Default")
      (node (ref "SW3") (pin "4") (pinfunction "S1_4") (pintype "passive"))
    )
    (net (code "146") (name "unconnected-(SW4-P1-Pad3)") (class "Default")
      (node (ref "SW4") (pin "3") (pinfunction "P1_3") (pintype "passive"))
    )
    (net (code "147") (name "unconnected-(SW4-S1-Pad4)") (class "Default")
      (node (ref "SW4") (pin "4") (pinfunction "S1_4") (pintype "passive"))
    )
    (net (code "148") (name "unconnected-(SW5-P1-Pad3)") (class "Default")
      (node (ref "SW5") (pin "3") (pinfunction "P1_3") (pintype "passive"))
    )
    (net (code "149") (name "unconnected-(SW5-S1-Pad4)") (class "Default")
      (node (ref "SW5") (pin "4") (pinfunction "S1_4") (pintype "passive"))
    )
    (net (code "150") (name "unconnected-(SW6-P1-Pad3)") (class "Default")
      (node (ref "SW6") (pin "3") (pinfunction "P1_3") (pintype "passive"))
    )
    (net (code "151") (name "unconnected-(SW6-S1-Pad4)") (class "Default")
      (node (ref "SW6") (pin "4") (pinfunction "S1_4") (pintype "passive"))
    )
    (net (code "152") (name "unconnected-(SW7-P1-Pad3)") (class "Default")
      (node (ref "SW7") (pin "3") (pinfunction "P1_3") (pintype "passive"))
    )
    (net (code "153") (name "unconnected-(SW7-S1-Pad4)") (class "Default")
      (node (ref "SW7") (pin "4") (pinfunction "S1_4") (pintype "passive"))
    )
    (net (code "154") (name "unconnected-(SW8-P1-Pad3)") (class "Default")
      (node (ref "SW8") (pin "3") (pinfunction "P1_3") (pintype "passive"))
    )
    (net (code "155") (name "unconnected-(SW8-S1-Pad4)") (class "Default")
      (node (ref "SW8") (pin "4") (pinfunction "S1_4") (pintype "passive"))
    )
    (net (code "156") (name "unconnected-(SW9-P1-Pad3)") (class "Default")
      (node (ref "SW9") (pin "3") (pinfunction "P1_3") (pintype "passive"))
    )
    (net (code "157") (name "unconnected-(SW9-S1-Pad4)") (class "Default")
      (node (ref "SW9") (pin "4") (pinfunction "S1_4") (pintype "passive"))
    )
    (net (code "158") (name "unconnected-(SW10-P1-Pad3)") (class "Default")
      (node (ref "SW10") (pin "3") (pinfunction "P1_3") (pintype "passive"))
    )
    (net (code "159") (name "unconnected-(SW10-S1-Pad4)") (class "Default")
      (node (ref "SW10") (pin "4") (pinfunction "S1_4") (pintype "passive"))
    )
    (net (code "160") (name "unconnected-(SW11-P1-Pad3)") (class "Default")
      (node (ref "SW11") (pin "3") (pinfunction "P1_3") (pintype "passive"))
    )
    (net (code "161") (name "unconnected-(SW11-S1-Pad4)") (class "Default")
      (node (ref "SW11") (pin "4") (pinfunction "S1_4") (pintype "passive"))
    )
    (net (code "162") (name "unconnected-(SW12-P1-Pad3)") (class "Default")
      (node (ref "SW12") (pin "3") (pinfunction "P1_3") (pintype "passive"))
    )
    (net (code "163") (name "unconnected-(SW12-S1-Pad4)") (class "Default")
      (node (ref "SW12") (pin "4") (pinfunction "S1_4") (pintype "passive"))
    )
    (net (code "164") (name "unconnected-(SW13-P1-Pad3)") (class "Default")
      (node (ref "SW13") (pin "3") (pinfunction "P1_3") (pintype "passive"))
    )
    (net (code "165") (name "unconnected-(SW13-S1-Pad4)") (class "Default")
      (node (ref "SW13") (pin "4") (pinfunction "S1_4") (pintype "passive"))
    )
    (net (code "166") (name "unconnected-(SW14-P1-Pad3)") (class "Default")
      (node (ref "SW14") (pin "3") (pinfunction "P1_3") (pintype "passive"))
    )
    (net (code "167") (name "unconnected-(SW14-S1-Pad4)") (class "Default")
      (node (ref "SW14") (pin "4") (pinfunction "S1_4") (pintype "passive"))
    )
    (net (code "168") (name "unconnected-(SW15-P1-Pad3)") (class "Default")
      (node (ref "SW15") (pin "3") (pinfunction "P1_3") (pintype "passive"))
    )
    (net (code "169") (name "unconnected-(SW15-S1-Pad4)") (class "Default")
      (node (ref "SW15") (pin "4") (pinfunction "S1_4") (pintype "passive"))
    )
    (net (code "170") (name "unconnected-(SW16-P1-Pad3)") (class "Default")
      (node (ref "SW16") (pin "3") (pinfunction "P1_3") (pintype "passive"))
    )
    (net (code "171") (name "unconnected-(SW16-S1-Pad4)") (class "Default")
      (node (ref "SW16") (pin "4") (pinfunction "S1_4") (pintype "passive"))
    )
  )
)
